# UI_mon.net
KiCad netlist of a schematic drawn in Altium Designer
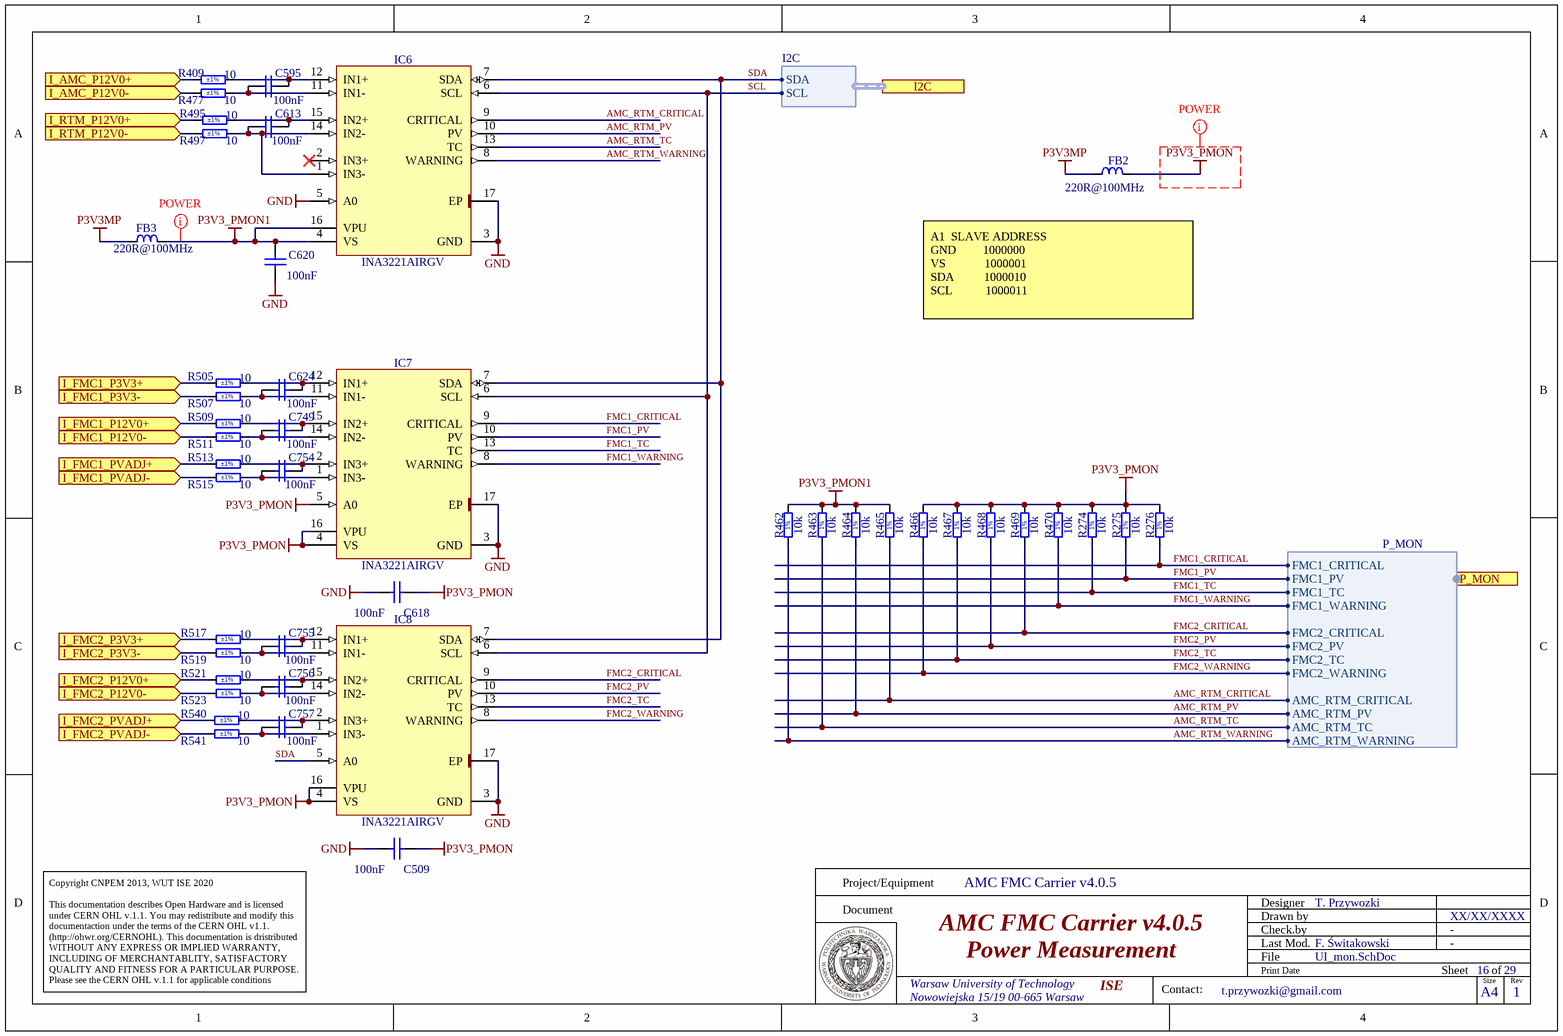
[diagram p0: UI_mon.SchDoc]

(export (version "E")
  (design (tool "Eeschema 10.0.6"))
  (components
    (comp (ref "C509")
      (value "100nF")
      (footprint "CAPC0603X33N")
      (description "Non-polarised capacitor")
      (fields
        (field (name "PART NUMBER") "CC0201_100NF_6.3V_10%_X5R")
        (field (name "VOLTAGE") "6.3V")
        (field (name "AUTHOR") "CERN DEM JLC")
      )
      (libsource (lib "Capacitors") (part "Capacitor - non polarized"))
    )
    (comp (ref "C595")
      (value "100nF")
      (footprint "CAPC0603X33N")
      (description "Non-polarised capacitor")
      (fields
        (field (name "PART NUMBER") "CC0201_100NF_6.3V_10%_X5R")
        (field (name "VOLTAGE") "6.3V")
        (field (name "AUTHOR") "CERN DEM JLC")
      )
      (libsource (lib "Capacitors") (part "Capacitor - non polarized"))
    )
    (comp (ref "C613")
      (value "100nF")
      (footprint "CAPC0603X33N")
      (description "Non-polarised capacitor")
      (fields
        (field (name "PART NUMBER") "CC0201_100NF_6.3V_10%_X5R")
        (field (name "VOLTAGE") "6.3V")
        (field (name "AUTHOR") "CERN DEM JLC")
      )
      (libsource (lib "Capacitors") (part "Capacitor - non polarized"))
    )
    (comp (ref "C618")
      (value "100nF")
      (footprint "CAPC0603X33N")
      (description "Non-polarised capacitor")
      (fields
        (field (name "PART NUMBER") "CC0201_100NF_6.3V_10%_X5R")
        (field (name "VOLTAGE") "6.3V")
        (field (name "AUTHOR") "CERN DEM JLC")
      )
      (libsource (lib "Capacitors") (part "Capacitor - non polarized"))
    )
    (comp (ref "C620")
      (value "100nF")
      (footprint "CAPC0603X33N")
      (description "Non-polarised capacitor")
      (fields
        (field (name "PART NUMBER") "CC0201_100NF_6.3V_10%_X5R")
        (field (name "VOLTAGE") "6.3V")
        (field (name "AUTHOR") "CERN DEM JLC")
      )
      (libsource (lib "Capacitors") (part "Capacitor - non polarized"))
    )
    (comp (ref "C624")
      (value "100nF")
      (footprint "CAPC0603X33N")
      (description "Non-polarised capacitor")
      (fields
        (field (name "PART NUMBER") "CC0201_100NF_6.3V_10%_X5R")
        (field (name "VOLTAGE") "6.3V")
        (field (name "AUTHOR") "CERN DEM JLC")
      )
      (libsource (lib "Capacitors") (part "Capacitor - non polarized"))
    )
    (comp (ref "C749")
      (value "100nF")
      (footprint "CAPC0603X33N")
      (description "Non-polarised capacitor")
      (fields
        (field (name "PART NUMBER") "CC0201_100NF_6.3V_10%_X5R")
        (field (name "VOLTAGE") "6.3V")
        (field (name "AUTHOR") "CERN DEM JLC")
      )
      (libsource (lib "Capacitors") (part "Capacitor - non polarized"))
    )
    (comp (ref "C754")
      (value "100nF")
      (footprint "CAPC0603X33N")
      (description "Non-polarised capacitor")
      (fields
        (field (name "PART NUMBER") "CC0201_100NF_6.3V_10%_X5R")
        (field (name "VOLTAGE") "6.3V")
        (field (name "AUTHOR") "CERN DEM JLC")
      )
      (libsource (lib "Capacitors") (part "Capacitor - non polarized"))
    )
    (comp (ref "C755")
      (value "100nF")
      (footprint "CAPC0603X33N")
      (description "Non-polarised capacitor")
      (fields
        (field (name "PART NUMBER") "CC0201_100NF_6.3V_10%_X5R")
        (field (name "VOLTAGE") "6.3V")
        (field (name "AUTHOR") "CERN DEM JLC")
      )
      (libsource (lib "Capacitors") (part "Capacitor - non polarized"))
    )
    (comp (ref "C756")
      (value "100nF")
      (footprint "CAPC0603X33N")
      (description "Non-polarised capacitor")
      (fields
        (field (name "PART NUMBER") "CC0201_100NF_6.3V_10%_X5R")
        (field (name "VOLTAGE") "6.3V")
        (field (name "AUTHOR") "CERN DEM JLC")
      )
      (libsource (lib "Capacitors") (part "Capacitor - non polarized"))
    )
    (comp (ref "C757")
      (value "100nF")
      (footprint "CAPC0603X33N")
      (description "Non-polarised capacitor")
      (fields
        (field (name "PART NUMBER") "CC0201_100NF_6.3V_10%_X5R")
        (field (name "VOLTAGE") "6.3V")
        (field (name "AUTHOR") "CERN DEM JLC")
      )
      (libsource (lib "Capacitors") (part "Capacitor - non polarized"))
    )
    (comp (ref "FB2")
      (value "220R@100MHz")
      (footprint "INDC2012X105N")
      (description "Inductor")
      (fields
        (field (name "PART NUMBER") "IND0805_MURATA_BLM21PG221SN1D")
        (field (name "POWER") "2A")
        (field (name "AUTHOR") "CERN DEM JLC")
      )
      (libsource (lib "Inductors & Transformers") (part "Inductor"))
    )
    (comp (ref "FB3")
      (value "220R@100MHz")
      (footprint "INDC2012X105N")
      (description "Inductor")
      (fields
        (field (name "PART NUMBER") "IND0805_MURATA_BLM21PG221SN1D")
        (field (name "POWER") "2A")
        (field (name "AUTHOR") "CERN DEM JLC")
      )
      (libsource (lib "Inductors & Transformers") (part "Inductor"))
    )
    (comp (ref "IC6")
      (value "INA3221AIRGV")
      (footprint "QFN65P400X400X100-17N-S225")
      (fields (field (name "MANUFACTURER") "TEXAS INSTRUMENTS") (field (name "AUTHOR") "CERN DEM MR"))
      (libsource (lib "ICs And Semiconductors") (part "INA3221"))
    )
    (comp (ref "IC7")
      (value "INA3221AIRGV")
      (footprint "QFN65P400X400X100-17N-S225")
      (fields (field (name "MANUFACTURER") "TEXAS INSTRUMENTS") (field (name "AUTHOR") "CERN DEM MR"))
      (libsource (lib "ICs And Semiconductors") (part "INA3221"))
    )
    (comp (ref "IC8")
      (value "INA3221AIRGV")
      (footprint "QFN65P400X400X100-17N-S225")
      (fields (field (name "MANUFACTURER") "TEXAS INSTRUMENTS") (field (name "AUTHOR") "CERN DEM MR"))
      (libsource (lib "ICs And Semiconductors") (part "INA3221"))
    )
    (comp (ref "R274")
      (value "10k")
      (footprint "RESC1005X40N")
      (description "Resistor - 1%")
      (fields
        (field (name "MANUFACTURER PART NUMBER") "R0402_10K_1%_0.0625W_100PPM")
        (field (name "MANUFACTURER") "GENERIC")
        (field (name "AUTHOR") "CERN DEM JLC")
      )
      (libsource (lib "Resistors") (part "Resistor - 1%"))
    )
    (comp (ref "R275")
      (value "10k")
      (footprint "RESC1005X40N")
      (description "Resistor - 1%")
      (fields
        (field (name "MANUFACTURER PART NUMBER") "R0402_10K_1%_0.0625W_100PPM")
        (field (name "MANUFACTURER") "GENERIC")
        (field (name "AUTHOR") "CERN DEM JLC")
      )
      (libsource (lib "Resistors") (part "Resistor - 1%"))
    )
    (comp (ref "R276")
      (value "10k")
      (footprint "RESC1005X40N")
      (description "Resistor - 1%")
      (fields
        (field (name "MANUFACTURER PART NUMBER") "R0402_10K_1%_0.0625W_100PPM")
        (field (name "MANUFACTURER") "GENERIC")
        (field (name "AUTHOR") "CERN DEM JLC")
      )
      (libsource (lib "Resistors") (part "Resistor - 1%"))
    )
    (comp (ref "R409")
      (value "10")
      (footprint "RESC1005X40N")
      (description "Resistor - 1%")
      (fields
        (field (name "TOLERANCE") "±1%")
        (field (name "PART NUMBER") "R0402_10R_1%_0.0625W_200PPM")
        (field (name "POWER") "0.0625W")
        (field (name "AUTHOR") "CERN DEM JLC")
      )
      (libsource (lib "Resistors") (part "Resistor - 1%"))
    )
    (comp (ref "R462")
      (value "10k")
      (footprint "RESC1005X40N")
      (description "Resistor - 1%")
      (fields
        (field (name "MANUFACTURER PART NUMBER") "R0402_10K_1%_0.0625W_100PPM")
        (field (name "MANUFACTURER") "GENERIC")
        (field (name "AUTHOR") "CERN DEM JLC")
      )
      (libsource (lib "Resistors") (part "Resistor - 1%"))
    )
    (comp (ref "R463")
      (value "10k")
      (footprint "RESC1005X40N")
      (description "Resistor - 1%")
      (fields
        (field (name "MANUFACTURER PART NUMBER") "R0402_10K_1%_0.0625W_100PPM")
        (field (name "MANUFACTURER") "GENERIC")
        (field (name "AUTHOR") "CERN DEM JLC")
      )
      (libsource (lib "Resistors") (part "Resistor - 1%"))
    )
    (comp (ref "R464")
      (value "10k")
      (footprint "RESC1005X40N")
      (description "Resistor - 1%")
      (fields
        (field (name "MANUFACTURER PART NUMBER") "R0402_10K_1%_0.0625W_100PPM")
        (field (name "MANUFACTURER") "GENERIC")
        (field (name "AUTHOR") "CERN DEM JLC")
      )
      (libsource (lib "Resistors") (part "Resistor - 1%"))
    )
    (comp (ref "R465")
      (value "10k")
      (footprint "RESC1005X40N")
      (description "Resistor - 1%")
      (fields
        (field (name "MANUFACTURER PART NUMBER") "R0402_10K_1%_0.0625W_100PPM")
        (field (name "MANUFACTURER") "GENERIC")
        (field (name "AUTHOR") "CERN DEM JLC")
      )
      (libsource (lib "Resistors") (part "Resistor - 1%"))
    )
    (comp (ref "R466")
      (value "10k")
      (footprint "RESC1005X40N")
      (description "Resistor - 1%")
      (fields
        (field (name "MANUFACTURER PART NUMBER") "R0402_10K_1%_0.0625W_100PPM")
        (field (name "MANUFACTURER") "GENERIC")
        (field (name "AUTHOR") "CERN DEM JLC")
      )
      (libsource (lib "Resistors") (part "Resistor - 1%"))
    )
    (comp (ref "R467")
      (value "10k")
      (footprint "RESC1005X40N")
      (description "Resistor - 1%")
      (fields
        (field (name "MANUFACTURER PART NUMBER") "R0402_10K_1%_0.0625W_100PPM")
        (field (name "MANUFACTURER") "GENERIC")
        (field (name "AUTHOR") "CERN DEM JLC")
      )
      (libsource (lib "Resistors") (part "Resistor - 1%"))
    )
    (comp (ref "R468")
      (value "10k")
      (footprint "RESC1005X40N")
      (description "Resistor - 1%")
      (fields
        (field (name "MANUFACTURER PART NUMBER") "R0402_10K_1%_0.0625W_100PPM")
        (field (name "MANUFACTURER") "GENERIC")
        (field (name "AUTHOR") "CERN DEM JLC")
      )
      (libsource (lib "Resistors") (part "Resistor - 1%"))
    )
    (comp (ref "R469")
      (value "10k")
      (footprint "RESC1005X40N")
      (description "Resistor - 1%")
      (fields
        (field (name "MANUFACTURER PART NUMBER") "R0402_10K_1%_0.0625W_100PPM")
        (field (name "MANUFACTURER") "GENERIC")
        (field (name "AUTHOR") "CERN DEM JLC")
      )
      (libsource (lib "Resistors") (part "Resistor - 1%"))
    )
    (comp (ref "R470")
      (value "10k")
      (footprint "RESC1005X40N")
      (description "Resistor - 1%")
      (fields
        (field (name "MANUFACTURER PART NUMBER") "R0402_10K_1%_0.0625W_100PPM")
        (field (name "MANUFACTURER") "GENERIC")
        (field (name "AUTHOR") "CERN DEM JLC")
      )
      (libsource (lib "Resistors") (part "Resistor - 1%"))
    )
    (comp (ref "R477")
      (value "10")
      (footprint "RESC1005X40N")
      (description "Resistor - 1%")
      (fields
        (field (name "TOLERANCE") "±1%")
        (field (name "PART NUMBER") "R0402_10R_1%_0.0625W_200PPM")
        (field (name "POWER") "0.0625W")
        (field (name "AUTHOR") "CERN DEM JLC")
      )
      (libsource (lib "Resistors") (part "Resistor - 1%"))
    )
    (comp (ref "R495")
      (value "10")
      (footprint "RESC1005X40N")
      (description "Resistor - 1%")
      (fields
        (field (name "TOLERANCE") "±1%")
        (field (name "PART NUMBER") "R0402_10R_1%_0.0625W_200PPM")
        (field (name "POWER") "0.0625W")
        (field (name "AUTHOR") "CERN DEM JLC")
      )
      (libsource (lib "Resistors") (part "Resistor - 1%"))
    )
    (comp (ref "R497")
      (value "10")
      (footprint "RESC1005X40N")
      (description "Resistor - 1%")
      (fields
        (field (name "TOLERANCE") "±1%")
        (field (name "PART NUMBER") "R0402_10R_1%_0.0625W_200PPM")
        (field (name "POWER") "0.0625W")
        (field (name "AUTHOR") "CERN DEM JLC")
      )
      (libsource (lib "Resistors") (part "Resistor - 1%"))
    )
    (comp (ref "R505")
      (value "10")
      (footprint "RESC1005X40N")
      (description "Resistor - 1%")
      (fields
        (field (name "TOLERANCE") "±1%")
        (field (name "PART NUMBER") "R0402_10R_1%_0.0625W_200PPM")
        (field (name "POWER") "0.0625W")
        (field (name "AUTHOR") "CERN DEM JLC")
      )
      (libsource (lib "Resistors") (part "Resistor - 1%"))
    )
    (comp (ref "R507")
      (value "10")
      (footprint "RESC1005X40N")
      (description "Resistor - 1%")
      (fields
        (field (name "TOLERANCE") "±1%")
        (field (name "PART NUMBER") "R0402_10R_1%_0.0625W_200PPM")
        (field (name "POWER") "0.0625W")
        (field (name "AUTHOR") "CERN DEM JLC")
      )
      (libsource (lib "Resistors") (part "Resistor - 1%"))
    )
    (comp (ref "R509")
      (value "10")
      (footprint "RESC1005X40N")
      (description "Resistor - 1%")
      (fields
        (field (name "TOLERANCE") "±1%")
        (field (name "PART NUMBER") "R0402_10R_1%_0.0625W_200PPM")
        (field (name "POWER") "0.0625W")
        (field (name "AUTHOR") "CERN DEM JLC")
      )
      (libsource (lib "Resistors") (part "Resistor - 1%"))
    )
    (comp (ref "R511")
      (value "10")
      (footprint "RESC1005X40N")
      (description "Resistor - 1%")
      (fields
        (field (name "TOLERANCE") "±1%")
        (field (name "PART NUMBER") "R0402_10R_1%_0.0625W_200PPM")
        (field (name "POWER") "0.0625W")
        (field (name "AUTHOR") "CERN DEM JLC")
      )
      (libsource (lib "Resistors") (part "Resistor - 1%"))
    )
    (comp (ref "R513")
      (value "10")
      (footprint "RESC1005X40N")
      (description "Resistor - 1%")
      (fields
        (field (name "TOLERANCE") "±1%")
        (field (name "PART NUMBER") "R0402_10R_1%_0.0625W_200PPM")
        (field (name "POWER") "0.0625W")
        (field (name "AUTHOR") "CERN DEM JLC")
      )
      (libsource (lib "Resistors") (part "Resistor - 1%"))
    )
    (comp (ref "R515")
      (value "10")
      (footprint "RESC1005X40N")
      (description "Resistor - 1%")
      (fields
        (field (name "TOLERANCE") "±1%")
        (field (name "PART NUMBER") "R0402_10R_1%_0.0625W_200PPM")
        (field (name "POWER") "0.0625W")
        (field (name "AUTHOR") "CERN DEM JLC")
      )
      (libsource (lib "Resistors") (part "Resistor - 1%"))
    )
    (comp (ref "R517")
      (value "10")
      (footprint "RESC1005X40N")
      (description "Resistor - 1%")
      (fields
        (field (name "TOLERANCE") "±1%")
        (field (name "PART NUMBER") "R0402_10R_1%_0.0625W_200PPM")
        (field (name "POWER") "0.0625W")
        (field (name "AUTHOR") "CERN DEM JLC")
      )
      (libsource (lib "Resistors") (part "Resistor - 1%"))
    )
    (comp (ref "R519")
      (value "10")
      (footprint "RESC1005X40N")
      (description "Resistor - 1%")
      (fields
        (field (name "TOLERANCE") "±1%")
        (field (name "PART NUMBER") "R0402_10R_1%_0.0625W_200PPM")
        (field (name "POWER") "0.0625W")
        (field (name "AUTHOR") "CERN DEM JLC")
      )
      (libsource (lib "Resistors") (part "Resistor - 1%"))
    )
    (comp (ref "R521")
      (value "10")
      (footprint "RESC1005X40N")
      (description "Resistor - 1%")
      (fields
        (field (name "TOLERANCE") "±1%")
        (field (name "PART NUMBER") "R0402_10R_1%_0.0625W_200PPM")
        (field (name "POWER") "0.0625W")
        (field (name "AUTHOR") "CERN DEM JLC")
      )
      (libsource (lib "Resistors") (part "Resistor - 1%"))
    )
    (comp (ref "R523")
      (value "10")
      (footprint "RESC1005X40N")
      (description "Resistor - 1%")
      (fields
        (field (name "TOLERANCE") "±1%")
        (field (name "PART NUMBER") "R0402_10R_1%_0.0625W_200PPM")
        (field (name "POWER") "0.0625W")
        (field (name "AUTHOR") "CERN DEM JLC")
      )
      (libsource (lib "Resistors") (part "Resistor - 1%"))
    )
    (comp (ref "R540")
      (value "10")
      (footprint "RESC1005X40N")
      (description "Resistor - 1%")
      (fields
        (field (name "TOLERANCE") "±1%")
        (field (name "PART NUMBER") "R0402_10R_1%_0.0625W_200PPM")
        (field (name "POWER") "0.0625W")
        (field (name "AUTHOR") "CERN DEM JLC")
      )
      (libsource (lib "Resistors") (part "Resistor - 1%"))
    )
    (comp (ref "R541")
      (value "10")
      (footprint "RESC1005X40N")
      (description "Resistor - 1%")
      (fields
        (field (name "TOLERANCE") "±1%")
        (field (name "PART NUMBER") "R0402_10R_1%_0.0625W_200PPM")
        (field (name "POWER") "0.0625W")
        (field (name "AUTHOR") "CERN DEM JLC")
      )
      (libsource (lib "Resistors") (part "Resistor - 1%"))
    )
  )
  (nets
    (net (code "3") (name "/AMC_RTM_CRITICAL") (class "Default")
      (node (ref "IC6") (pin "9") (pinfunction "CRITICAL_9") (pintype "output"))
      (node (ref "R465") (pin "1") (pinfunction "1_1") (pintype "passive"))
    )
    (net (code "4") (name "/AMC_RTM_PV") (class "Default")
      (node (ref "IC6") (pin "10") (pinfunction "PV_10") (pintype "output"))
      (node (ref "R464") (pin "1") (pinfunction "1_1") (pintype "passive"))
    )
    (net (code "5") (name "/AMC_RTM_TC") (class "Default")
      (node (ref "IC6") (pin "13") (pinfunction "TC_13") (pintype "output"))
      (node (ref "R463") (pin "1") (pinfunction "1_1") (pintype "passive"))
    )
    (net (code "6") (name "/AMC_RTM_WARNING") (class "Default")
      (node (ref "IC6") (pin "8") (pinfunction "WARNING_8") (pintype "output"))
      (node (ref "R462") (pin "1") (pinfunction "1_1") (pintype "passive"))
    )
    (net (code "7") (name "/FMC1_CRITICAL") (class "Default")
      (node (ref "IC7") (pin "9") (pinfunction "CRITICAL_9") (pintype "output"))
      (node (ref "R276") (pin "1") (pinfunction "1_1") (pintype "passive"))
    )
    (net (code "8") (name "/FMC1_PV") (class "Default")
      (node (ref "IC7") (pin "10") (pinfunction "PV_10") (pintype "output"))
      (node (ref "R275") (pin "1") (pinfunction "1_1") (pintype "passive"))
    )
    (net (code "9") (name "/FMC1_TC") (class "Default")
      (node (ref "IC7") (pin "13") (pinfunction "TC_13") (pintype "output"))
      (node (ref "R274") (pin "1") (pinfunction "1_1") (pintype "passive"))
    )
    (net (code "10") (name "/FMC1_WARNING") (class "Default")
      (node (ref "IC7") (pin "8") (pinfunction "WARNING_8") (pintype "output"))
      (node (ref "R470") (pin "1") (pinfunction "1_1") (pintype "passive"))
    )
    (net (code "11") (name "/FMC2_CRITICAL") (class "Default")
      (node (ref "IC8") (pin "9") (pinfunction "CRITICAL_9") (pintype "output"))
      (node (ref "R469") (pin "1") (pinfunction "1_1") (pintype "passive"))
    )
    (net (code "12") (name "/FMC2_PV") (class "Default")
      (node (ref "IC8") (pin "10") (pinfunction "PV_10") (pintype "output"))
      (node (ref "R468") (pin "1") (pinfunction "1_1") (pintype "passive"))
    )
    (net (code "13") (name "/FMC2_TC") (class "Default")
      (node (ref "IC8") (pin "13") (pinfunction "TC_13") (pintype "output"))
      (node (ref "R467") (pin "1") (pinfunction "1_1") (pintype "passive"))
    )
    (net (code "14") (name "/FMC2_WARNING") (class "Default")
      (node (ref "IC8") (pin "8") (pinfunction "WARNING_8") (pintype "output"))
      (node (ref "R466") (pin "1") (pinfunction "1_1") (pintype "passive"))
    )
    (net (code "15") (name "/I_AMC_P12V0+") (class "Default")
      (node (ref "R409") (pin "1") (pinfunction "1_1") (pintype "passive"))
    )
    (net (code "16") (name "/I_AMC_P12V0-") (class "Default")
      (node (ref "R477") (pin "1") (pinfunction "1_1") (pintype "passive"))
    )
    (net (code "17") (name "/I_FMC1_P3V3+") (class "Default")
      (node (ref "R505") (pin "1") (pinfunction "1_1") (pintype "passive"))
    )
    (net (code "18") (name "/I_FMC1_P3V3-") (class "Default")
      (node (ref "R507") (pin "1") (pinfunction "1_1") (pintype "passive"))
    )
    (net (code "19") (name "/I_FMC1_P12V0+") (class "Default")
      (node (ref "R509") (pin "1") (pinfunction "1_1") (pintype "passive"))
    )
    (net (code "20") (name "/I_FMC1_P12V0-") (class "Default")
      (node (ref "R511") (pin "1") (pinfunction "1_1") (pintype "passive"))
    )
    (net (code "21") (name "/I_FMC1_PVADJ+") (class "Default")
      (node (ref "R513") (pin "1") (pinfunction "1_1") (pintype "passive"))
    )
    (net (code "22") (name "/I_FMC1_PVADJ-") (class "Default")
      (node (ref "R515") (pin "1") (pinfunction "1_1") (pintype "passive"))
    )
    (net (code "23") (name "/I_FMC2_P3V3+") (class "Default")
      (node (ref "R517") (pin "1") (pinfunction "1_1") (pintype "passive"))
    )
    (net (code "24") (name "/I_FMC2_P3V3-") (class "Default")
      (node (ref "R519") (pin "1") (pinfunction "1_1") (pintype "passive"))
    )
    (net (code "25") (name "/I_FMC2_P12V0+") (class "Default")
      (node (ref "R521") (pin "1") (pinfunction "1_1") (pintype "passive"))
    )
    (net (code "26") (name "/I_FMC2_P12V0-") (class "Default")
      (node (ref "R523") (pin "1") (pinfunction "1_1") (pintype "passive"))
    )
    (net (code "27") (name "/I_FMC2_PVADJ+") (class "Default")
      (node (ref "R540") (pin "1") (pinfunction "1_1") (pintype "passive"))
    )
    (net (code "28") (name "/I_FMC2_PVADJ-") (class "Default")
      (node (ref "R541") (pin "1") (pinfunction "1_1") (pintype "passive"))
    )
    (net (code "29") (name "/I_RTM_P12V0+") (class "Default")
      (node (ref "R495") (pin "1") (pinfunction "1_1") (pintype "passive"))
    )
    (net (code "30") (name "/I_RTM_P12V0-") (class "Default")
      (node (ref "R497") (pin "1") (pinfunction "1_1") (pintype "passive"))
    )
    (net (code "31") (name "/SCL") (class "Default")
      (node (ref "IC6") (pin "6") (pinfunction "SCL_6") (pintype "input"))
      (node (ref "IC7") (pin "6") (pinfunction "SCL_6") (pintype "input"))
      (node (ref "IC8") (pin "6") (pinfunction "SCL_6") (pintype "input"))
    )
    (net (code "32") (name "/SDA") (class "Default")
      (node (ref "IC6") (pin "7") (pinfunction "SDA_7") (pintype "bidirectional"))
      (node (ref "IC7") (pin "7") (pinfunction "SDA_7") (pintype "bidirectional"))
      (node (ref "IC8") (pin "5") (pinfunction "A0_5") (pintype "input"))
      (node (ref "IC8") (pin "7") (pinfunction "SDA_7") (pintype "bidirectional"))
    )
    (net (code "35") (name "GND") (class "Default")
      (node (ref "C509") (pin "2") (pinfunction "2_2") (pintype "passive"))
      (node (ref "C618") (pin "2") (pinfunction "2_2") (pintype "passive"))
      (node (ref "C620") (pin "2") (pinfunction "2_2") (pintype "passive"))
      (node (ref "IC6") (pin "17") (pinfunction "EP_17") (pintype "power_in"))
      (node (ref "IC6") (pin "3") (pinfunction "GND_3") (pintype "power_in"))
      (node (ref "IC6") (pin "5") (pinfunction "A0_5") (pintype "input"))
      (node (ref "IC7") (pin "17") (pinfunction "EP_17") (pintype "power_in"))
      (node (ref "IC7") (pin "3") (pinfunction "GND_3") (pintype "power_in"))
      (node (ref "IC8") (pin "17") (pinfunction "EP_17") (pintype "power_in"))
      (node (ref "IC8") (pin "3") (pinfunction "GND_3") (pintype "power_in"))
    )
    (net (code "36") (name "Net-(IC6-IN1+)") (class "Default")
      (node (ref "C595") (pin "2") (pinfunction "2_2") (pintype "passive"))
      (node (ref "IC6") (pin "12") (pinfunction "IN1+_12") (pintype "input"))
      (node (ref "R409") (pin "2") (pinfunction "2_2") (pintype "passive"))
    )
    (net (code "37") (name "Net-(IC6-IN1-)") (class "Default")
      (node (ref "C595") (pin "1") (pinfunction "1_1") (pintype "passive"))
      (node (ref "IC6") (pin "11") (pinfunction "IN1-_11") (pintype "input"))
      (node (ref "R477") (pin "2") (pinfunction "2_2") (pintype "passive"))
    )
    (net (code "38") (name "Net-(IC6-IN2+)") (class "Default")
      (node (ref "C613") (pin "2") (pinfunction "2_2") (pintype "passive"))
      (node (ref "IC6") (pin "15") (pinfunction "IN2+_15") (pintype "input"))
      (node (ref "R495") (pin "2") (pinfunction "2_2") (pintype "passive"))
    )
    (net (code "39") (name "Net-(IC6-IN2-)") (class "Default")
      (node (ref "C613") (pin "1") (pinfunction "1_1") (pintype "passive"))
      (node (ref "IC6") (pin "1") (pinfunction "IN3-_1") (pintype "input"))
      (node (ref "IC6") (pin "14") (pinfunction "IN2-_14") (pintype "input"))
      (node (ref "R497") (pin "2") (pinfunction "2_2") (pintype "passive"))
    )
    (net (code "40") (name "Net-(IC7-IN1+)") (class "Default")
      (node (ref "C624") (pin "2") (pinfunction "2_2") (pintype "passive"))
      (node (ref "IC7") (pin "12") (pinfunction "IN1+_12") (pintype "input"))
      (node (ref "R505") (pin "2") (pinfunction "2_2") (pintype "passive"))
    )
    (net (code "41") (name "Net-(IC7-IN1-)") (class "Default")
      (node (ref "C624") (pin "1") (pinfunction "1_1") (pintype "passive"))
      (node (ref "IC7") (pin "11") (pinfunction "IN1-_11") (pintype "input"))
      (node (ref "R507") (pin "2") (pinfunction "2_2") (pintype "passive"))
    )
    (net (code "42") (name "Net-(IC7-IN2+)") (class "Default")
      (node (ref "C749") (pin "2") (pinfunction "2_2") (pintype "passive"))
      (node (ref "IC7") (pin "15") (pinfunction "IN2+_15") (pintype "input"))
      (node (ref "R509") (pin "2") (pinfunction "2_2") (pintype "passive"))
    )
    (net (code "43") (name "Net-(IC7-IN2-)") (class "Default")
      (node (ref "C749") (pin "1") (pinfunction "1_1") (pintype "passive"))
      (node (ref "IC7") (pin "14") (pinfunction "IN2-_14") (pintype "input"))
      (node (ref "R511") (pin "2") (pinfunction "2_2") (pintype "passive"))
    )
    (net (code "44") (name "Net-(IC7-IN3+)") (class "Default")
      (node (ref "C754") (pin "2") (pinfunction "2_2") (pintype "passive"))
      (node (ref "IC7") (pin "2") (pinfunction "IN3+_2") (pintype "input"))
      (node (ref "R513") (pin "2") (pinfunction "2_2") (pintype "passive"))
    )
    (net (code "45") (name "Net-(IC7-IN3-)") (class "Default")
      (node (ref "C754") (pin "1") (pinfunction "1_1") (pintype "passive"))
      (node (ref "IC7") (pin "1") (pinfunction "IN3-_1") (pintype "input"))
      (node (ref "R515") (pin "2") (pinfunction "2_2") (pintype "passive"))
    )
    (net (code "46") (name "Net-(IC8-IN1+)") (class "Default")
      (node (ref "C755") (pin "2") (pinfunction "2_2") (pintype "passive"))
      (node (ref "IC8") (pin "12") (pinfunction "IN1+_12") (pintype "input"))
      (node (ref "R517") (pin "2") (pinfunction "2_2") (pintype "passive"))
    )
    (net (code "47") (name "Net-(IC8-IN1-)") (class "Default")
      (node (ref "C755") (pin "1") (pinfunction "1_1") (pintype "passive"))
      (node (ref "IC8") (pin "11") (pinfunction "IN1-_11") (pintype "input"))
      (node (ref "R519") (pin "2") (pinfunction "2_2") (pintype "passive"))
    )
    (net (code "48") (name "Net-(IC8-IN2+)") (class "Default")
      (node (ref "C756") (pin "2") (pinfunction "2_2") (pintype "passive"))
      (node (ref "IC8") (pin "15") (pinfunction "IN2+_15") (pintype "input"))
      (node (ref "R521") (pin "2") (pinfunction "2_2") (pintype "passive"))
    )
    (net (code "49") (name "Net-(IC8-IN2-)") (class "Default")
      (node (ref "C756") (pin "1") (pinfunction "1_1") (pintype "passive"))
      (node (ref "IC8") (pin "14") (pinfunction "IN2-_14") (pintype "input"))
      (node (ref "R523") (pin "2") (pinfunction "2_2") (pintype "passive"))
    )
    (net (code "50") (name "Net-(IC8-IN3+)") (class "Default")
      (node (ref "C757") (pin "2") (pinfunction "2_2") (pintype "passive"))
      (node (ref "IC8") (pin "2") (pinfunction "IN3+_2") (pintype "input"))
      (node (ref "R540") (pin "2") (pinfunction "2_2") (pintype "passive"))
    )
    (net (code "51") (name "Net-(IC8-IN3-)") (class "Default")
      (node (ref "C757") (pin "1") (pinfunction "1_1") (pintype "passive"))
      (node (ref "IC8") (pin "1") (pinfunction "IN3-_1") (pintype "input"))
      (node (ref "R541") (pin "2") (pinfunction "2_2") (pintype "passive"))
    )
    (net (code "52") (name "P3V3MP") (class "Default")
      (node (ref "FB2") (pin "1") (pinfunction "1_1") (pintype "passive"))
      (node (ref "FB3") (pin "1") (pinfunction "1_1") (pintype "passive"))
    )
    (net (code "53") (name "P3V3_PMON") (class "Default")
      (node (ref "C509") (pin "1") (pinfunction "1_1") (pintype "passive"))
      (node (ref "C618") (pin "1") (pinfunction "1_1") (pintype "passive"))
      (node (ref "FB2") (pin "2") (pinfunction "2_2") (pintype "passive"))
      (node (ref "IC7") (pin "16") (pinfunction "VPU_16") (pintype "power_in"))
      (node (ref "IC7") (pin "4") (pinfunction "VS_4") (pintype "power_in"))
      (node (ref "IC7") (pin "5") (pinfunction "A0_5") (pintype "input"))
      (node (ref "IC8") (pin "16") (pinfunction "VPU_16") (pintype "power_in"))
      (node (ref "IC8") (pin "4") (pinfunction "VS_4") (pintype "power_in"))
      (node (ref "R274") (pin "2") (pinfunction "2_2") (pintype "passive"))
      (node (ref "R275") (pin "2") (pinfunction "2_2") (pintype "passive"))
      (node (ref "R276") (pin "2") (pinfunction "2_2") (pintype "passive"))
      (node (ref "R466") (pin "2") (pinfunction "2_2") (pintype "passive"))
      (node (ref "R467") (pin "2") (pinfunction "2_2") (pintype "passive"))
      (node (ref "R468") (pin "2") (pinfunction "2_2") (pintype "passive"))
      (node (ref "R469") (pin "2") (pinfunction "2_2") (pintype "passive"))
      (node (ref "R470") (pin "2") (pinfunction "2_2") (pintype "passive"))
    )
    (net (code "54") (name "P3V3_PMON1") (class "Default")
      (node (ref "C620") (pin "1") (pinfunction "1_1") (pintype "passive"))
      (node (ref "FB3") (pin "2") (pinfunction "2_2") (pintype "passive"))
      (node (ref "IC6") (pin "16") (pinfunction "VPU_16") (pintype "power_in"))
      (node (ref "IC6") (pin "4") (pinfunction "VS_4") (pintype "power_in"))
      (node (ref "R462") (pin "2") (pinfunction "2_2") (pintype "passive"))
      (node (ref "R463") (pin "2") (pinfunction "2_2") (pintype "passive"))
      (node (ref "R464") (pin "2") (pinfunction "2_2") (pintype "passive"))
      (node (ref "R465") (pin "2") (pinfunction "2_2") (pintype "passive"))
    )
    (net (code "55") (name "unconnected-(IC6-IN3+-Pad2)") (class "Default")
      (node (ref "IC6") (pin "2") (pinfunction "IN3+_2") (pintype "input+no_connect"))
    )
  )
)
